# TSL238_breakout.net
KiCad netlist of a schematic drawn in EAGLE
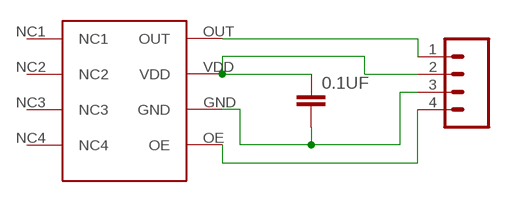
[diagram p0: schematic, sheet 1]

(export (version "E")
  (design (tool "Eeschema 10.0.6"))
  (components
    (comp (ref "0.1UF")
      (value "CAP0603-CAP")
      (footprint "eagle-import:0603-CAP")
      (libsource (lib "eagle-import") (part "CAP0603-CAP"))
    )
    (comp (ref "J1")
      (value "M04PTH")
      (footprint "eagle-import:1X04")
      (libsource (lib "eagle-import") (part "M04PTH"))
    )
    (comp (ref "U$1")
      (value "TSL238")
      (footprint "eagle-import:TSL238")
      (libsource (lib "eagle-import") (part "TSL238"))
    )
  )
  (nets
    (net (code "1") (name "Net-(0.1UF-Pad1)") (class "Default")
      (node (ref "0.1UF") (pin "1") (pinfunction "1_1") (pintype "passive"))
      (node (ref "J1") (pin "2") (pinfunction "2_2") (pintype "passive"))
      (node (ref "U$1") (pin "VDD") (pinfunction "VDD_VDD") (pintype "bidirectional"))
    )
    (net (code "2") (name "Net-(0.1UF-Pad2)") (class "Default")
      (node (ref "0.1UF") (pin "2") (pinfunction "2_2") (pintype "passive"))
      (node (ref "J1") (pin "3") (pinfunction "3_3") (pintype "passive"))
      (node (ref "U$1") (pin "GND") (pinfunction "GND_GND") (pintype "bidirectional"))
    )
    (net (code "3") (name "Net-(J1-Pad1)") (class "Default")
      (node (ref "J1") (pin "1") (pinfunction "1_1") (pintype "passive"))
      (node (ref "U$1") (pin "OUT") (pinfunction "OUT_OUT") (pintype "bidirectional"))
    )
    (net (code "4") (name "Net-(J1-Pad4)") (class "Default")
      (node (ref "J1") (pin "4") (pinfunction "4_4") (pintype "passive"))
      (node (ref "U$1") (pin "OE") (pinfunction "OE_OE") (pintype "bidirectional"))
    )
    (net (code "5") (name "unconnected-(U$1-PadNC1)") (class "Default")
      (node (ref "U$1") (pin "NC1") (pinfunction "NC1_NC1") (pintype "bidirectional"))
    )
    (net (code "6") (name "unconnected-(U$1-PadNC2)") (class "Default")
      (node (ref "U$1") (pin "NC2") (pinfunction "NC2_NC2") (pintype "bidirectional"))
    )
    (net (code "7") (name "unconnected-(U$1-PadNC3)") (class "Default")
      (node (ref "U$1") (pin "NC3") (pinfunction "NC3_NC3") (pintype "bidirectional"))
    )
    (net (code "8") (name "unconnected-(U$1-PadNC4)") (class "Default")
      (node (ref "U$1") (pin "NC4") (pinfunction "NC4_NC4") (pintype "bidirectional"))
    )
  )
)
